# macplus.net
KiCad netlist of a schematic drawn in EAGLE
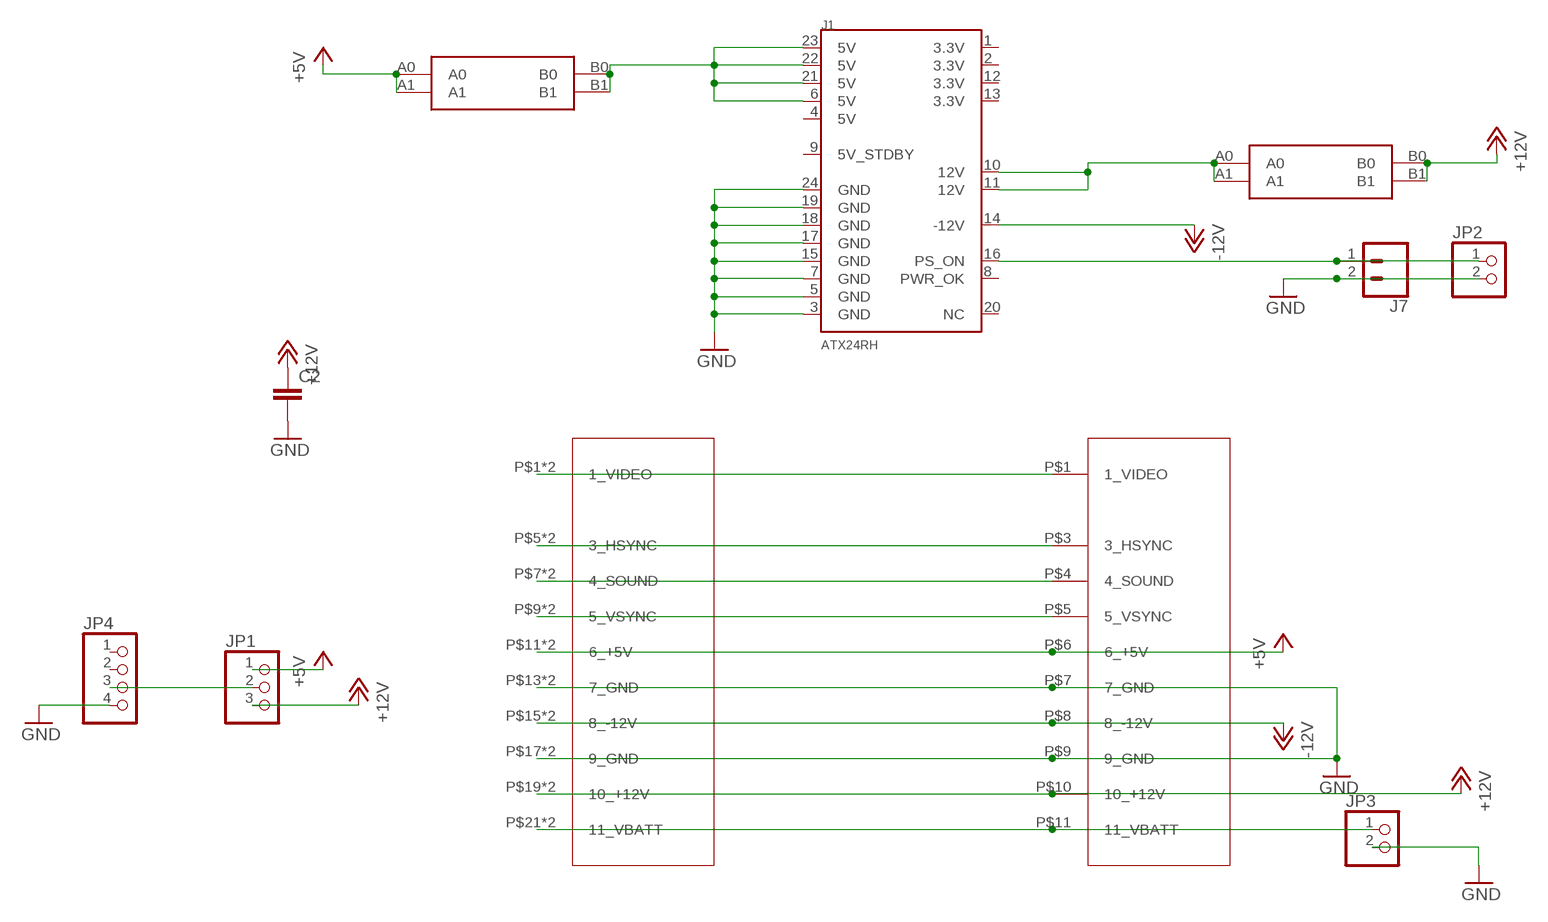
[diagram p0: schematic, sheet 1]

(export (version "E")
  (design (tool "Eeschema 10.0.6"))
  (components
    (comp (ref "C2")
      (value "C5/2.5")
      (footprint "eagle-import:C5B2.5")
      (libsource (lib "eagle-import") (part "C5/2.5"))
    )
    (comp (ref "J1")
      (value "ATX24RH")
      (footprint "eagle-import:ATX24_STRAIGHT")
      (libsource (lib "eagle-import") (part "ATX24RH"))
    )
    (comp (ref "J7")
      (value "CONN_023.5MM-NO_SILK")
      (footprint "eagle-import:SCREWTERMINAL-3.5MM-2-NS")
      (libsource (lib "eagle-import") (part "CONN_023.5MM-NO_SILK"))
    )
    (comp (ref "JP1")
      (value "PINHD-1X3")
      (footprint "eagle-import:1X03")
      (libsource (lib "eagle-import") (part "PINHD-1X3"))
    )
    (comp (ref "JP2")
      (value "PINHD-1X2")
      (footprint "eagle-import:1X02")
      (libsource (lib "eagle-import") (part "PINHD-1X2"))
    )
    (comp (ref "JP3")
      (value "PINHD-1X2")
      (footprint "eagle-import:1X02")
      (libsource (lib "eagle-import") (part "PINHD-1X2"))
    )
    (comp (ref "JP4")
      (value "PINHD-1X4")
      (footprint "eagle-import:1X04")
      (libsource (lib "eagle-import") (part "PINHD-1X4"))
    )
    (comp (ref "U$1")
      (value "MACPLUS")
      (footprint "eagle-import:396_10P")
      (libsource (lib "eagle-import") (part "MACPLUS"))
    )
    (comp (ref "U$2")
      (value "CAR_FUSE_HOLDER3IN1")
      (footprint "eagle-import:FUSE_HOLDER_3IN1")
      (libsource (lib "eagle-import") (part "CAR_FUSE_HOLDER3IN1"))
    )
    (comp (ref "U$3")
      (value "3.96_FEM")
      (footprint "eagle-import:3.96_FEMALE_GAP")
      (libsource (lib "eagle-import") (part "3.96_FEM"))
    )
    (comp (ref "U$8")
      (value "CAR_FUSE_HOLDER3IN1")
      (footprint "eagle-import:FUSE_HOLDER_3IN1")
      (libsource (lib "eagle-import") (part "CAR_FUSE_HOLDER3IN1"))
    )
  )
  (nets
    (net (code "1") (name "+5V") (class "Default")
      (node (ref "JP1") (pin "1") (pinfunction "1_1") (pintype "passive"))
      (node (ref "U$1") (pin "P$6") (pinfunction "6_+5V_P$6") (pintype "bidirectional"))
      (node (ref "U$3") (pin "P$11") (pinfunction "6_+5V_P$11") (pintype "bidirectional"))
      (node (ref "U$3") (pin "P$12") (pinfunction "6_+5V_P$12") (pintype "bidirectional"))
      (node (ref "U$8") (pin "A0") (pinfunction "A0_A0") (pintype "bidirectional"))
      (node (ref "U$8") (pin "A1") (pinfunction "A1_A1") (pintype "bidirectional"))
    )
    (net (code "2") (name "+12V") (class "Default")
      (node (ref "C2") (pin "1") (pinfunction "1_1") (pintype "passive"))
      (node (ref "JP1") (pin "3") (pinfunction "3_3") (pintype "passive"))
      (node (ref "U$1") (pin "P$10") (pinfunction "10_+12V_P$10") (pintype "bidirectional"))
      (node (ref "U$2") (pin "B0") (pinfunction "B0_B0") (pintype "bidirectional"))
      (node (ref "U$2") (pin "B1") (pinfunction "B1_B1") (pintype "bidirectional"))
      (node (ref "U$3") (pin "P$19") (pinfunction "10_+12V_P$19") (pintype "bidirectional"))
      (node (ref "U$3") (pin "P$20") (pinfunction "10_+12V_P$20") (pintype "bidirectional"))
    )
    (net (code "3") (name "-12V") (class "Default")
      (node (ref "J1") (pin "14") (pinfunction "-12V_14") (pintype "bidirectional"))
      (node (ref "U$1") (pin "P$8") (pinfunction "8_-12V_P$8") (pintype "bidirectional"))
      (node (ref "U$3") (pin "P$15") (pinfunction "8_-12V_P$15") (pintype "bidirectional"))
      (node (ref "U$3") (pin "P$16") (pinfunction "8_-12V_P$16") (pintype "bidirectional"))
    )
    (net (code "4") (name "GND") (class "Default")
      (node (ref "C2") (pin "2") (pinfunction "2_2") (pintype "passive"))
      (node (ref "J1") (pin "15") (pinfunction "GND_15") (pintype "bidirectional"))
      (node (ref "J1") (pin "17") (pinfunction "GND_17") (pintype "bidirectional"))
      (node (ref "J1") (pin "18") (pinfunction "GND_18") (pintype "bidirectional"))
      (node (ref "J1") (pin "19") (pinfunction "GND_19") (pintype "bidirectional"))
      (node (ref "J1") (pin "24") (pinfunction "GND_24") (pintype "bidirectional"))
      (node (ref "J1") (pin "3") (pinfunction "GND_3") (pintype "bidirectional"))
      (node (ref "J1") (pin "5") (pinfunction "GND_5") (pintype "bidirectional"))
      (node (ref "J1") (pin "7") (pinfunction "GND_7") (pintype "bidirectional"))
      (node (ref "J7") (pin "2") (pinfunction "2_2") (pintype "passive"))
      (node (ref "JP2") (pin "2") (pinfunction "2_2") (pintype "passive"))
      (node (ref "JP3") (pin "2") (pinfunction "2_2") (pintype "passive"))
      (node (ref "JP4") (pin "4") (pinfunction "4_4") (pintype "passive"))
      (node (ref "U$1") (pin "P$7") (pinfunction "7_GND_P$7") (pintype "bidirectional"))
      (node (ref "U$1") (pin "P$9") (pinfunction "9_GND_P$9") (pintype "bidirectional"))
      (node (ref "U$3") (pin "P$13") (pinfunction "7_GND_P$13") (pintype "bidirectional"))
      (node (ref "U$3") (pin "P$14") (pinfunction "7_GND_P$14") (pintype "bidirectional"))
      (node (ref "U$3") (pin "P$17") (pinfunction "9_GND_P$17") (pintype "bidirectional"))
      (node (ref "U$3") (pin "P$18") (pinfunction "9_GND_P$18") (pintype "bidirectional"))
    )
    (net (code "5") (name "Net-(J1-5V-Pad21)") (class "Default")
      (node (ref "J1") (pin "21") (pinfunction "5V_21") (pintype "bidirectional"))
      (node (ref "J1") (pin "22") (pinfunction "5V_22") (pintype "bidirectional"))
      (node (ref "J1") (pin "23") (pinfunction "5V_23") (pintype "bidirectional"))
      (node (ref "J1") (pin "6") (pinfunction "5V_6") (pintype "bidirectional"))
      (node (ref "U$8") (pin "B0") (pinfunction "B0_B0") (pintype "bidirectional"))
      (node (ref "U$8") (pin "B1") (pinfunction "B1_B1") (pintype "bidirectional"))
    )
    (net (code "6") (name "Net-(J1-12V-Pad10)") (class "Default")
      (node (ref "J1") (pin "10") (pinfunction "12V_10") (pintype "bidirectional"))
      (node (ref "J1") (pin "11") (pinfunction "12V_11") (pintype "bidirectional"))
      (node (ref "U$2") (pin "A0") (pinfunction "A0_A0") (pintype "bidirectional"))
      (node (ref "U$2") (pin "A1") (pinfunction "A1_A1") (pintype "bidirectional"))
    )
    (net (code "7") (name "Net-(J1-PS_ON)") (class "Default")
      (node (ref "J1") (pin "16") (pinfunction "PS_ON_16") (pintype "bidirectional"))
      (node (ref "J7") (pin "1") (pinfunction "1_1") (pintype "passive"))
      (node (ref "JP2") (pin "1") (pinfunction "1_1") (pintype "passive"))
    )
    (net (code "8") (name "Net-(JP1-Pad2)") (class "Default")
      (node (ref "JP1") (pin "2") (pinfunction "2_2") (pintype "passive"))
      (node (ref "JP4") (pin "3") (pinfunction "3_3") (pintype "passive"))
    )
    (net (code "9") (name "Net-(U$1-1_VIDEO)") (class "Default")
      (node (ref "U$1") (pin "P$1") (pinfunction "1_VIDEO_P$1") (pintype "bidirectional"))
      (node (ref "U$3") (pin "P$1") (pinfunction "1_VIDEO_P$1") (pintype "bidirectional"))
      (node (ref "U$3") (pin "P$2") (pinfunction "1_VIDEO_P$2") (pintype "bidirectional"))
    )
    (net (code "10") (name "Net-(U$1-3_HSYNC)") (class "Default")
      (node (ref "U$1") (pin "P$3") (pinfunction "3_HSYNC_P$3") (pintype "bidirectional"))
      (node (ref "U$3") (pin "P$5") (pinfunction "3_HSYNC_P$5") (pintype "bidirectional"))
      (node (ref "U$3") (pin "P$6") (pinfunction "3_HSYNC_P$6") (pintype "bidirectional"))
    )
    (net (code "11") (name "Net-(U$1-4_SOUND)") (class "Default")
      (node (ref "U$1") (pin "P$4") (pinfunction "4_SOUND_P$4") (pintype "bidirectional"))
      (node (ref "U$3") (pin "P$7") (pinfunction "4_SOUND_P$7") (pintype "bidirectional"))
      (node (ref "U$3") (pin "P$8") (pinfunction "4_SOUND_P$8") (pintype "bidirectional"))
    )
    (net (code "12") (name "Net-(U$1-5_VSYNC)") (class "Default")
      (node (ref "U$1") (pin "P$5") (pinfunction "5_VSYNC_P$5") (pintype "bidirectional"))
      (node (ref "U$3") (pin "P$10") (pinfunction "5_VSYNC_P$10") (pintype "bidirectional"))
      (node (ref "U$3") (pin "P$9") (pinfunction "5_VSYNC_P$9") (pintype "bidirectional"))
    )
    (net (code "13") (name "Net-(U$1-11_VBATT)") (class "Default")
      (node (ref "JP3") (pin "1") (pinfunction "1_1") (pintype "passive"))
      (node (ref "U$1") (pin "P$11") (pinfunction "11_VBATT_P$11") (pintype "bidirectional"))
      (node (ref "U$3") (pin "P$21") (pinfunction "11_VBATT_P$21") (pintype "bidirectional"))
      (node (ref "U$3") (pin "P$22") (pinfunction "11_VBATT_P$22") (pintype "bidirectional"))
    )
    (net (code "14") (name "unconnected-(J1-3.3V-Pad1)") (class "Default")
      (node (ref "J1") (pin "1") (pinfunction "3.3V_1") (pintype "bidirectional"))
    )
    (net (code "15") (name "unconnected-(J1-3.3V-Pad2)") (class "Default")
      (node (ref "J1") (pin "2") (pinfunction "3.3V_2") (pintype "bidirectional"))
    )
    (net (code "16") (name "unconnected-(J1-3.3V-Pad12)") (class "Default")
      (node (ref "J1") (pin "12") (pinfunction "3.3V_12") (pintype "bidirectional"))
    )
    (net (code "17") (name "unconnected-(J1-3.3V-Pad13)") (class "Default")
      (node (ref "J1") (pin "13") (pinfunction "3.3V_13") (pintype "bidirectional"))
    )
    (net (code "18") (name "unconnected-(J1-5V-Pad4)") (class "Default")
      (node (ref "J1") (pin "4") (pinfunction "5V_4") (pintype "bidirectional"))
    )
    (net (code "19") (name "unconnected-(J1-5V_STDBY-Pad9)") (class "Default")
      (node (ref "J1") (pin "9") (pinfunction "5V_STDBY_9") (pintype "bidirectional"))
    )
    (net (code "20") (name "unconnected-(J1-NC-Pad20)") (class "Default")
      (node (ref "J1") (pin "20") (pinfunction "NC_20") (pintype "bidirectional"))
    )
    (net (code "21") (name "unconnected-(J1-PWR_OK-Pad8)") (class "Default")
      (node (ref "J1") (pin "8") (pinfunction "PWR_OK_8") (pintype "bidirectional"))
    )
    (net (code "22") (name "unconnected-(JP4-Pad1)") (class "Default")
      (node (ref "JP4") (pin "1") (pinfunction "1_1") (pintype "passive"))
    )
    (net (code "23") (name "unconnected-(JP4-Pad2)") (class "Default")
      (node (ref "JP4") (pin "2") (pinfunction "2_2") (pintype "passive"))
    )
  )
)
